# Kill.net
KiCad netlist of a schematic drawn in Altium Designer
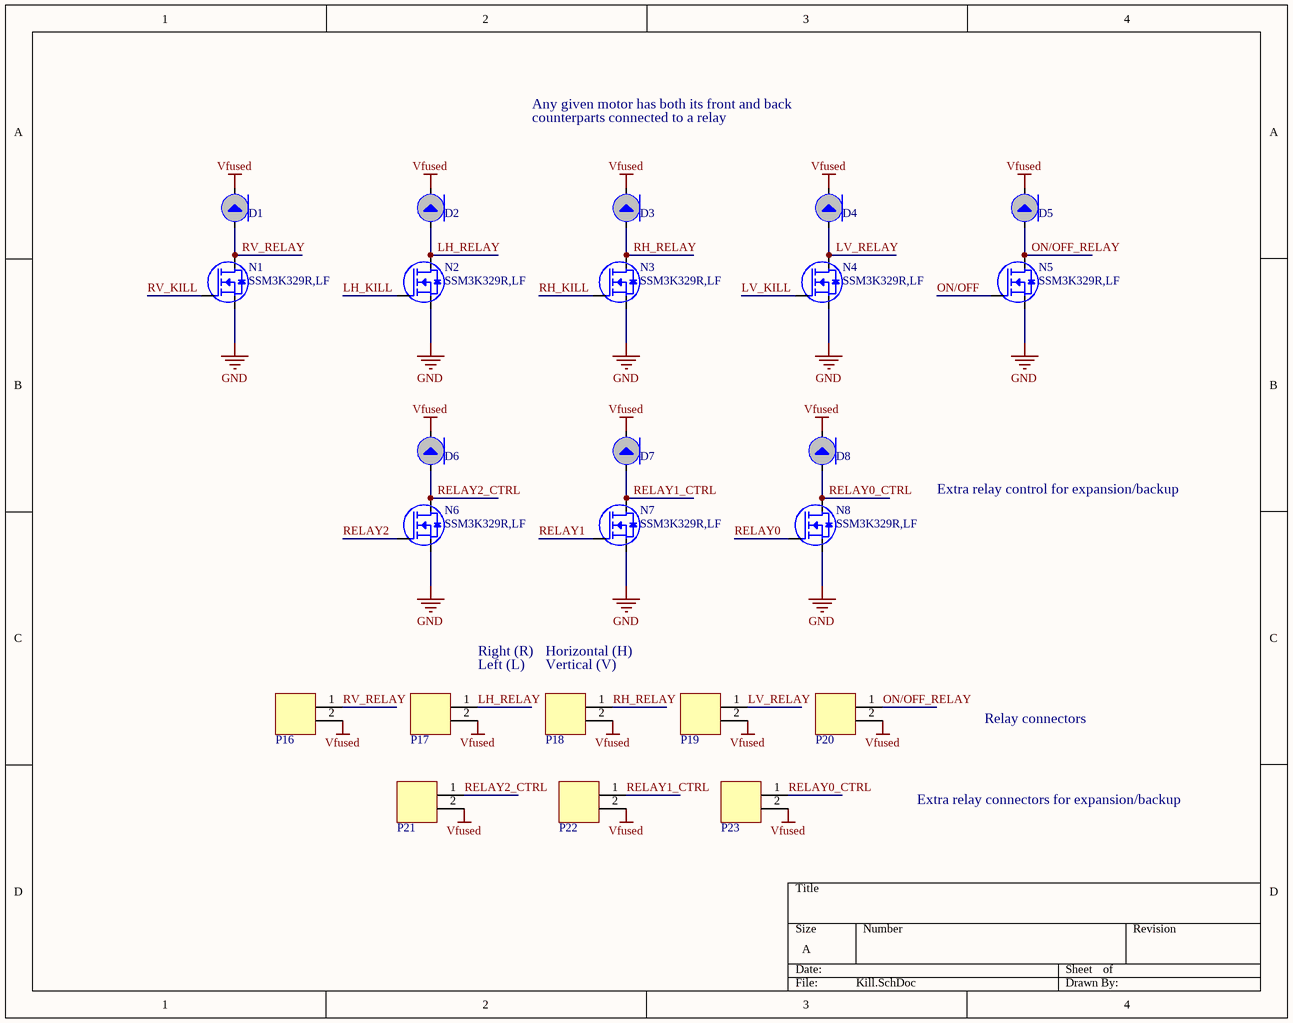
[diagram p0: Kill.SchDoc]

(export (version "E")
  (design (tool "Eeschema 10.0.6"))
  (components
    (comp (ref "D1")
      (value "Diode")
      (footprint "TEMD5510FX01")
      (description "Standard Diode Template")
      (libsource (lib "SubjuGator8") (part "Diode"))
    )
    (comp (ref "D2")
      (value "Diode")
      (footprint "TEMD5510FX01")
      (description "Standard Diode Template")
      (libsource (lib "SubjuGator8") (part "Diode"))
    )
    (comp (ref "D3")
      (value "Diode")
      (footprint "TEMD5510FX01")
      (description "Standard Diode Template")
      (libsource (lib "SubjuGator8") (part "Diode"))
    )
    (comp (ref "D4")
      (value "Diode")
      (footprint "TEMD5510FX01")
      (description "Standard Diode Template")
      (libsource (lib "SubjuGator8") (part "Diode"))
    )
    (comp (ref "D5")
      (value "Diode")
      (footprint "TEMD5510FX01")
      (description "Standard Diode Template")
      (libsource (lib "SubjuGator8") (part "Diode"))
    )
    (comp (ref "D6")
      (value "Diode")
      (footprint "TEMD5510FX01")
      (description "Standard Diode Template")
      (libsource (lib "SubjuGator8") (part "Diode"))
    )
    (comp (ref "D7")
      (value "Diode")
      (footprint "TEMD5510FX01")
      (description "Standard Diode Template")
      (libsource (lib "SubjuGator8") (part "Diode"))
    )
    (comp (ref "D8")
      (value "Diode")
      (footprint "TEMD5510FX01")
      (description "Standard Diode Template")
      (libsource (lib "SubjuGator8") (part "Diode"))
    )
    (comp (ref "N1")
      (value "SSM3K329R,LF")
      (footprint "SSM3K329R,LF")
      (description "MOSFET N CH 30V 3.5A 2-3Z1A")
      (libsource (lib "SubjuGator8") (part "SSM3K329R,LF"))
    )
    (comp (ref "N2")
      (value "SSM3K329R,LF")
      (footprint "SSM3K329R,LF")
      (description "MOSFET N CH 30V 3.5A 2-3Z1A")
      (libsource (lib "SubjuGator8") (part "SSM3K329R,LF"))
    )
    (comp (ref "N3")
      (value "SSM3K329R,LF")
      (footprint "SSM3K329R,LF")
      (description "MOSFET N CH 30V 3.5A 2-3Z1A")
      (libsource (lib "SubjuGator8") (part "SSM3K329R,LF"))
    )
    (comp (ref "N4")
      (value "SSM3K329R,LF")
      (footprint "SSM3K329R,LF")
      (description "MOSFET N CH 30V 3.5A 2-3Z1A")
      (libsource (lib "SubjuGator8") (part "SSM3K329R,LF"))
    )
    (comp (ref "N5")
      (value "SSM3K329R,LF")
      (footprint "SSM3K329R,LF")
      (description "MOSFET N CH 30V 3.5A 2-3Z1A")
      (libsource (lib "SubjuGator8") (part "SSM3K329R,LF"))
    )
    (comp (ref "N6")
      (value "SSM3K329R,LF")
      (footprint "SSM3K329R,LF")
      (description "MOSFET N CH 30V 3.5A 2-3Z1A")
      (libsource (lib "SubjuGator8") (part "SSM3K329R,LF"))
    )
    (comp (ref "N7")
      (value "SSM3K329R,LF")
      (footprint "SSM3K329R,LF")
      (description "MOSFET N CH 30V 3.5A 2-3Z1A")
      (libsource (lib "SubjuGator8") (part "SSM3K329R,LF"))
    )
    (comp (ref "N8")
      (value "SSM3K329R,LF")
      (footprint "SSM3K329R,LF")
      (description "MOSFET N CH 30V 3.5A 2-3Z1A")
      (libsource (lib "SubjuGator8") (part "SSM3K329R,LF"))
    )
    (comp (ref "P16")
      (value "2-pin Vert Sherlock")
      (footprint "MOLEX-HDR-1X2-SHERLOCK-VERT")
      (libsource (lib "SubjuGator8") (part "MOLEX-HDR-1x2-SHERLOCK_VERT"))
    )
    (comp (ref "P17")
      (value "2-pin Vert Sherlock")
      (footprint "MOLEX-HDR-1X2-SHERLOCK-VERT")
      (libsource (lib "SubjuGator8") (part "MOLEX-HDR-1x2-SHERLOCK_VERT"))
    )
    (comp (ref "P18")
      (value "2-pin Vert Sherlock")
      (footprint "MOLEX-HDR-1X2-SHERLOCK-VERT")
      (libsource (lib "SubjuGator8") (part "MOLEX-HDR-1x2-SHERLOCK_VERT"))
    )
    (comp (ref "P19")
      (value "2-pin Vert Sherlock")
      (footprint "MOLEX-HDR-1X2-SHERLOCK-VERT")
      (libsource (lib "SubjuGator8") (part "MOLEX-HDR-1x2-SHERLOCK_VERT"))
    )
    (comp (ref "P20")
      (value "2-pin Vert Sherlock")
      (footprint "MOLEX-HDR-1X2-SHERLOCK-VERT")
      (libsource (lib "SubjuGator8") (part "MOLEX-HDR-1x2-SHERLOCK_VERT"))
    )
    (comp (ref "P21")
      (value "2-pin Vert Sherlock")
      (footprint "MOLEX-HDR-1X2-SHERLOCK-VERT")
      (libsource (lib "SubjuGator8") (part "MOLEX-HDR-1x2-SHERLOCK_VERT"))
    )
    (comp (ref "P22")
      (value "2-pin Vert Sherlock")
      (footprint "MOLEX-HDR-1X2-SHERLOCK-VERT")
      (libsource (lib "SubjuGator8") (part "MOLEX-HDR-1x2-SHERLOCK_VERT"))
    )
    (comp (ref "P23")
      (value "2-pin Vert Sherlock")
      (footprint "MOLEX-HDR-1X2-SHERLOCK-VERT")
      (libsource (lib "SubjuGator8") (part "MOLEX-HDR-1x2-SHERLOCK_VERT"))
    )
  )
  (nets
    (net (code "1") (name "/LH_KILL") (class "Default")
      (node (ref "N2") (pin "1") (pinfunction "G_1") (pintype "passive"))
    )
    (net (code "2") (name "/LH_RELAY") (class "Default")
      (node (ref "D2") (pin "A") (pinfunction "A_A") (pintype "passive"))
      (node (ref "N2") (pin "3") (pinfunction "D_3") (pintype "passive"))
      (node (ref "P17") (pin "1") (pinfunction "1_1") (pintype "passive"))
    )
    (net (code "3") (name "/LV_KILL") (class "Default")
      (node (ref "N4") (pin "1") (pinfunction "G_1") (pintype "passive"))
    )
    (net (code "4") (name "/LV_RELAY") (class "Default")
      (node (ref "D4") (pin "A") (pinfunction "A_A") (pintype "passive"))
      (node (ref "N4") (pin "3") (pinfunction "D_3") (pintype "passive"))
      (node (ref "P19") (pin "1") (pinfunction "1_1") (pintype "passive"))
    )
    (net (code "5") (name "/ON{slash}OFF") (class "Default")
      (node (ref "N5") (pin "1") (pinfunction "G_1") (pintype "passive"))
    )
    (net (code "6") (name "/ON{slash}OFF_RELAY") (class "Default")
      (node (ref "D5") (pin "A") (pinfunction "A_A") (pintype "passive"))
      (node (ref "N5") (pin "3") (pinfunction "D_3") (pintype "passive"))
      (node (ref "P20") (pin "1") (pinfunction "1_1") (pintype "passive"))
    )
    (net (code "7") (name "/RELAY0") (class "Default")
      (node (ref "N8") (pin "1") (pinfunction "G_1") (pintype "passive"))
    )
    (net (code "8") (name "/RELAY0_CTRL") (class "Default")
      (node (ref "D8") (pin "A") (pinfunction "A_A") (pintype "passive"))
      (node (ref "N8") (pin "3") (pinfunction "D_3") (pintype "passive"))
      (node (ref "P23") (pin "1") (pinfunction "1_1") (pintype "passive"))
    )
    (net (code "9") (name "/RELAY1") (class "Default")
      (node (ref "N7") (pin "1") (pinfunction "G_1") (pintype "passive"))
    )
    (net (code "10") (name "/RELAY1_CTRL") (class "Default")
      (node (ref "D7") (pin "A") (pinfunction "A_A") (pintype "passive"))
      (node (ref "N7") (pin "3") (pinfunction "D_3") (pintype "passive"))
      (node (ref "P22") (pin "1") (pinfunction "1_1") (pintype "passive"))
    )
    (net (code "11") (name "/RELAY2") (class "Default")
      (node (ref "N6") (pin "1") (pinfunction "G_1") (pintype "passive"))
    )
    (net (code "12") (name "/RELAY2_CTRL") (class "Default")
      (node (ref "D6") (pin "A") (pinfunction "A_A") (pintype "passive"))
      (node (ref "N6") (pin "3") (pinfunction "D_3") (pintype "passive"))
      (node (ref "P21") (pin "1") (pinfunction "1_1") (pintype "passive"))
    )
    (net (code "13") (name "/RH_KILL") (class "Default")
      (node (ref "N3") (pin "1") (pinfunction "G_1") (pintype "passive"))
    )
    (net (code "14") (name "/RH_RELAY") (class "Default")
      (node (ref "D3") (pin "A") (pinfunction "A_A") (pintype "passive"))
      (node (ref "N3") (pin "3") (pinfunction "D_3") (pintype "passive"))
      (node (ref "P18") (pin "1") (pinfunction "1_1") (pintype "passive"))
    )
    (net (code "15") (name "/RV_KILL") (class "Default")
      (node (ref "N1") (pin "1") (pinfunction "G_1") (pintype "passive"))
    )
    (net (code "16") (name "/RV_RELAY") (class "Default")
      (node (ref "D1") (pin "A") (pinfunction "A_A") (pintype "passive"))
      (node (ref "N1") (pin "3") (pinfunction "D_3") (pintype "passive"))
      (node (ref "P16") (pin "1") (pinfunction "1_1") (pintype "passive"))
    )
    (net (code "17") (name "GND") (class "Default")
      (node (ref "N1") (pin "2") (pinfunction "S_2") (pintype "passive"))
      (node (ref "N2") (pin "2") (pinfunction "S_2") (pintype "passive"))
      (node (ref "N3") (pin "2") (pinfunction "S_2") (pintype "passive"))
      (node (ref "N4") (pin "2") (pinfunction "S_2") (pintype "passive"))
      (node (ref "N5") (pin "2") (pinfunction "S_2") (pintype "passive"))
      (node (ref "N6") (pin "2") (pinfunction "S_2") (pintype "passive"))
      (node (ref "N7") (pin "2") (pinfunction "S_2") (pintype "passive"))
      (node (ref "N8") (pin "2") (pinfunction "S_2") (pintype "passive"))
    )
    (net (code "18") (name "Vfused") (class "Default")
      (node (ref "D1") (pin "C") (pinfunction "C_C") (pintype "passive"))
      (node (ref "D2") (pin "C") (pinfunction "C_C") (pintype "passive"))
      (node (ref "D3") (pin "C") (pinfunction "C_C") (pintype "passive"))
      (node (ref "D4") (pin "C") (pinfunction "C_C") (pintype "passive"))
      (node (ref "D5") (pin "C") (pinfunction "C_C") (pintype "passive"))
      (node (ref "D6") (pin "C") (pinfunction "C_C") (pintype "passive"))
      (node (ref "D7") (pin "C") (pinfunction "C_C") (pintype "passive"))
      (node (ref "D8") (pin "C") (pinfunction "C_C") (pintype "passive"))
      (node (ref "P16") (pin "2") (pinfunction "2_2") (pintype "passive"))
      (node (ref "P17") (pin "2") (pinfunction "2_2") (pintype "passive"))
      (node (ref "P18") (pin "2") (pinfunction "2_2") (pintype "passive"))
      (node (ref "P19") (pin "2") (pinfunction "2_2") (pintype "passive"))
      (node (ref "P20") (pin "2") (pinfunction "2_2") (pintype "passive"))
      (node (ref "P21") (pin "2") (pinfunction "2_2") (pintype "passive"))
      (node (ref "P22") (pin "2") (pinfunction "2_2") (pintype "passive"))
      (node (ref "P23") (pin "2") (pinfunction "2_2") (pintype "passive"))
    )
  )
)
